# Wireless_ECG_Monitor.net
KiCad netlist of a schematic drawn in Altium Designer
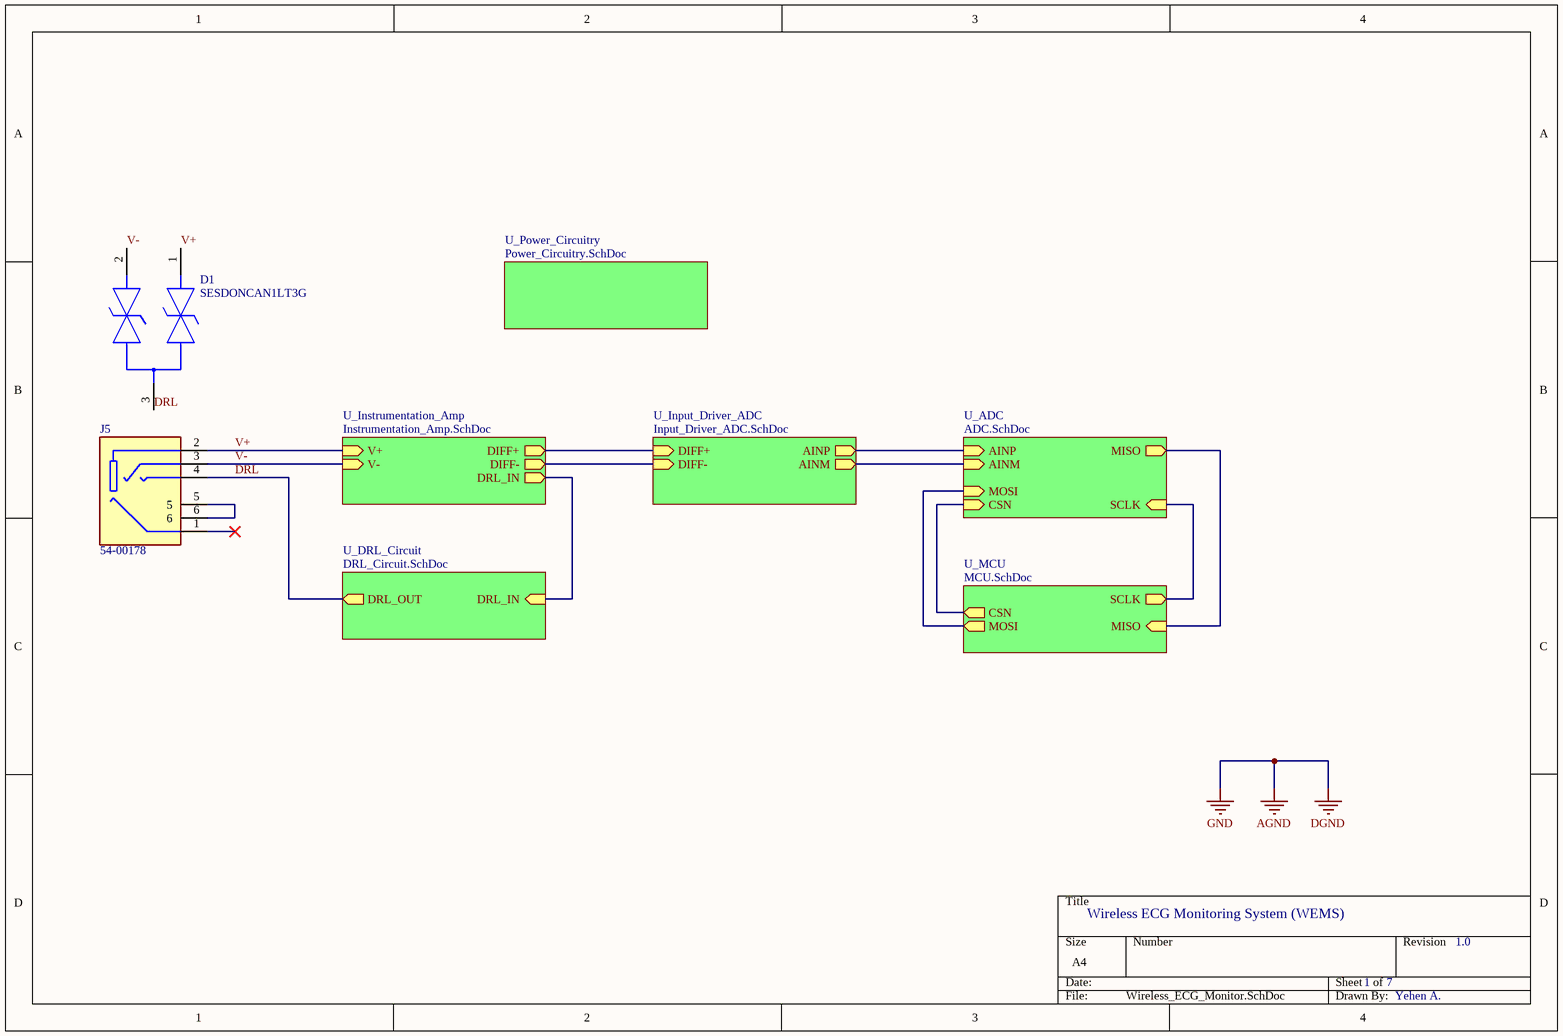
[diagram p0: Wireless_ECG_Monitor.SchDoc]

(export (version "E")
  (design (tool "Eeschema 10.0.6"))
  (components
    (comp (ref "D1")
      (value "SESDONCAN1LT3G")
      (footprint "FP-318-MFG")
      (description "SESDONCAN1LT3G ESD Suppressor Diode TVS Bi-Dir 24V Automotive 3-Pin SOT-23 T/R")
      (libsource (lib "Altium Content Vault") (part "d67acf977b83acdcd755a8d3ca90334"))
    )
    (comp (ref "J5")
      (value "54-00178")
      (footprint "54-00178")
      (description "Conn Jack Stereo 3.5MM SMD R/a")
      (fields (field (name "MANUFACTURER") "Tensility"))
      (libsource (lib "Schlib1") (part "54-00178"))
    )
  )
  (nets
    (net (code "6") (name "/DRL") (class "Default")
      (node (ref "D1") (pin "3") (pinfunction "3_3") (pintype "passive"))
      (node (ref "J5") (pin "4") (pinfunction "4_4") (pintype "passive"))
    )
    (net (code "11") (name "/V+") (class "Default")
      (node (ref "D1") (pin "1") (pinfunction "1_1") (pintype "passive"))
      (node (ref "J5") (pin "2") (pinfunction "2_2") (pintype "passive"))
    )
    (net (code "12") (name "/V-") (class "Default")
      (node (ref "D1") (pin "2") (pinfunction "2_2") (pintype "passive"))
      (node (ref "J5") (pin "3") (pinfunction "3_3") (pintype "passive"))
    )
    (net (code "14") (name "Net-(J5-Pad5)") (class "Default")
      (node (ref "J5") (pin "5") (pinfunction "5_5") (pintype "passive"))
      (node (ref "J5") (pin "6") (pinfunction "6_6") (pintype "passive"))
    )
    (net (code "15") (name "unconnected-(J5-Pad1)") (class "Default")
      (node (ref "J5") (pin "1") (pinfunction "1_1") (pintype "passive+no_connect"))
    )
  )
)
